# pms.net
KiCad netlist of a schematic drawn in EAGLE
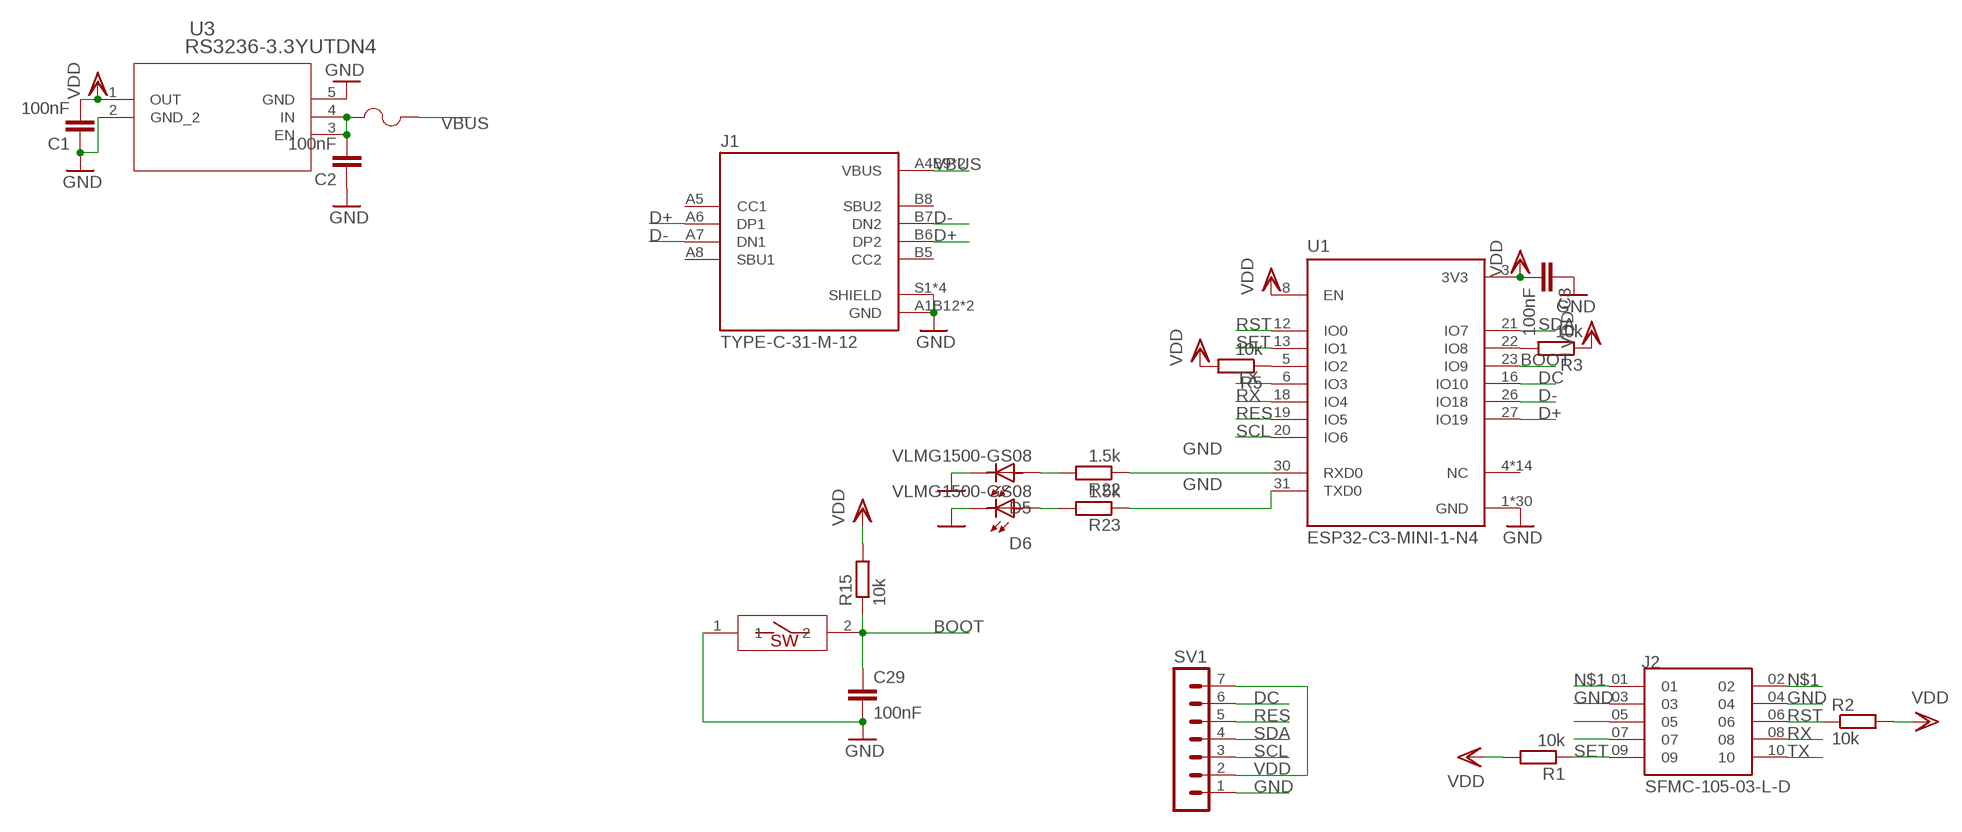
[diagram p0: schematic, sheet 1]

(export (version "E")
  (design (tool "Eeschema 10.0.6"))
  (components
    (comp (ref "C1")
      (value "100nF")
      (footprint "eagle-import:C0402")
      (libsource (lib "eagle-import") (part "CC0402"))
    )
    (comp (ref "C2")
      (value "100nF")
      (footprint "eagle-import:C0402")
      (libsource (lib "eagle-import") (part "CC0402"))
    )
    (comp (ref "C3")
      (value "100nF")
      (footprint "eagle-import:C0402")
      (libsource (lib "eagle-import") (part "CC0402"))
    )
    (comp (ref "C29")
      (value "100nF")
      (footprint "eagle-import:C0402")
      (libsource (lib "eagle-import") (part "CC0402"))
    )
    (comp (ref "D5")
      (value "VLMG1500-GS08")
      (footprint "eagle-import:LEDC1005X35N")
      (fields (field (name "MF") "Vishay"))
      (libsource (lib "eagle-import") (part "VLMG1500-GS08"))
    )
    (comp (ref "D6")
      (value "VLMG1500-GS08")
      (footprint "eagle-import:LEDC1005X35N")
      (fields (field (name "MF") "Vishay"))
      (libsource (lib "eagle-import") (part "VLMG1500-GS08"))
    )
    (comp (ref "F2")
      (value "1210L050YR1210LSERIES_LTF-L")
      (footprint "eagle-import:1210LSERIES_LTF-L")
      (fields (field (name "MANUFACTURER_PART_NUMBER") "1210L050YR"))
      (libsource (lib "eagle-import") (part "1210L050YR1210LSERIES_LTF-L"))
    )
    (comp (ref "J1")
      (value "TYPE-C-31-M-12")
      (footprint "eagle-import:HRO_TYPE-C-31-M-12")
      (fields (field (name "MF") "HRO Electronics Co., Ltd."))
      (libsource (lib "eagle-import") (part "TYPE-C-31-M-12"))
    )
    (comp (ref "J2")
      (value "SFMC-105-03-L-D")
      (footprint "eagle-import:SAMTEC_SFMC-105-03-L-D")
      (fields (field (name "MF") "Samtec"))
      (libsource (lib "eagle-import") (part "SFMC-105-03-L-D"))
    )
    (comp (ref "R1")
      (value "10k")
      (footprint "eagle-import:R0402")
      (libsource (lib "eagle-import") (part "RR0402"))
    )
    (comp (ref "R2")
      (value "10k")
      (footprint "eagle-import:R0402")
      (libsource (lib "eagle-import") (part "RR0402"))
    )
    (comp (ref "R3")
      (value "10k")
      (footprint "eagle-import:R0402")
      (libsource (lib "eagle-import") (part "RR0402"))
    )
    (comp (ref "R5")
      (value "10k")
      (footprint "eagle-import:R0402")
      (libsource (lib "eagle-import") (part "RR0402"))
    )
    (comp (ref "R15")
      (value "10k")
      (footprint "eagle-import:R0402")
      (libsource (lib "eagle-import") (part "RR0402"))
    )
    (comp (ref "R22")
      (value "1.5k")
      (footprint "eagle-import:R0402")
      (libsource (lib "eagle-import") (part "RR0402"))
    )
    (comp (ref "R23")
      (value "1.5k")
      (footprint "eagle-import:R0402")
      (libsource (lib "eagle-import") (part "RR0402"))
    )
    (comp (ref "RESET")
      (value "SMDSWITCH")
      (footprint "eagle-import:RESC4217X170")
      (libsource (lib "eagle-import") (part "SMDSWITCH"))
    )
    (comp (ref "SV1")
      (value "MA07-1")
      (footprint "eagle-import:MA07-1")
      (libsource (lib "eagle-import") (part "MA07-1"))
    )
    (comp (ref "U1")
      (value "ESP32-C3-MINI-1-N4")
      (footprint "eagle-import:XCVR_ESP32-C3-MINI-1-N4")
      (fields (field (name "MF") "Espressif Systems"))
      (libsource (lib "eagle-import") (part "ESP32-C3-MINI-1-N4"))
    )
    (comp (ref "U3")
      (value "RS3236-3.3YUTDN4")
      (footprint "eagle-import:UTDFN-1X1-4_JRT")
      (fields (field (name "COPYRIGHT") "Copyright (C) 2022 Ultra Librarian. All rights reserved."))
      (libsource (lib "eagle-import") (part "RS3236-3.3YUTDN4"))
    )
  )
  (nets
    (net (code "1") (name "/BOOT") (class "Default")
      (node (ref "C29") (pin "1") (pinfunction "1_1") (pintype "passive"))
      (node (ref "R15") (pin "1") (pinfunction "1_1") (pintype "passive"))
      (node (ref "RESET") (pin "2") (pinfunction "2_2") (pintype "bidirectional"))
      (node (ref "U1") (pin "23") (pinfunction "IO9_23") (pintype "bidirectional"))
    )
    (net (code "2") (name "/D+") (class "Default")
      (node (ref "J1") (pin "A6") (pinfunction "DP1_A6") (pintype "bidirectional"))
      (node (ref "J1") (pin "B6") (pinfunction "DP2_B6") (pintype "bidirectional"))
      (node (ref "U1") (pin "27") (pinfunction "IO19_27") (pintype "bidirectional"))
    )
    (net (code "3") (name "/D-") (class "Default")
      (node (ref "J1") (pin "A7") (pinfunction "DN1_A7") (pintype "bidirectional"))
      (node (ref "J1") (pin "B7") (pinfunction "DN2_B7") (pintype "bidirectional"))
      (node (ref "U1") (pin "26") (pinfunction "IO18_26") (pintype "bidirectional"))
    )
    (net (code "4") (name "/DC") (class "Default")
      (node (ref "SV1") (pin "6") (pinfunction "6_6") (pintype "passive"))
      (node (ref "U1") (pin "16") (pinfunction "IO10_16") (pintype "bidirectional"))
    )
    (net (code "5") (name "/N$1") (class "Default")
      (node (ref "C2") (pin "2") (pinfunction "2_2") (pintype "passive"))
      (node (ref "F2") (pin "2") (pinfunction "2_2") (pintype "passive"))
      (node (ref "J2") (pin "01") (pinfunction "01_01") (pintype "passive"))
      (node (ref "J2") (pin "02") (pinfunction "02_02") (pintype "passive"))
      (node (ref "U3") (pin "3") (pinfunction "EN_3") (pintype "input"))
      (node (ref "U3") (pin "4") (pinfunction "IN_4") (pintype "power_in"))
    )
    (net (code "6") (name "/RES") (class "Default")
      (node (ref "SV1") (pin "5") (pinfunction "5_5") (pintype "passive"))
      (node (ref "U1") (pin "19") (pinfunction "IO5_19") (pintype "bidirectional"))
    )
    (net (code "7") (name "/RST") (class "Default")
      (node (ref "J2") (pin "06") (pinfunction "06_06") (pintype "passive"))
      (node (ref "R2") (pin "1") (pinfunction "1_1") (pintype "passive"))
      (node (ref "U1") (pin "12") (pinfunction "IO0_12") (pintype "bidirectional"))
    )
    (net (code "8") (name "/RX") (class "Default")
      (node (ref "J2") (pin "08") (pinfunction "08_08") (pintype "passive"))
      (node (ref "U1") (pin "18") (pinfunction "IO4_18") (pintype "bidirectional"))
    )
    (net (code "9") (name "/SCL") (class "Default")
      (node (ref "SV1") (pin "3") (pinfunction "3_3") (pintype "passive"))
      (node (ref "U1") (pin "20") (pinfunction "IO6_20") (pintype "bidirectional"))
    )
    (net (code "10") (name "/SDA") (class "Default")
      (node (ref "SV1") (pin "4") (pinfunction "4_4") (pintype "passive"))
      (node (ref "U1") (pin "21") (pinfunction "IO7_21") (pintype "bidirectional"))
    )
    (net (code "11") (name "/SET") (class "Default")
      (node (ref "J2") (pin "09") (pinfunction "09_09") (pintype "passive"))
      (node (ref "R1") (pin "1") (pinfunction "1_1") (pintype "passive"))
      (node (ref "U1") (pin "13") (pinfunction "IO1_13") (pintype "bidirectional"))
    )
    (net (code "12") (name "/TX") (class "Default")
      (node (ref "J2") (pin "10") (pinfunction "10_10") (pintype "passive"))
      (node (ref "U1") (pin "6") (pinfunction "IO3_6") (pintype "bidirectional"))
    )
    (net (code "13") (name "/VBUS") (class "Default")
      (node (ref "F2") (pin "1") (pinfunction "1_1") (pintype "passive"))
      (node (ref "J1") (pin "A4B9") (pinfunction "VBUS_A4B9") (pintype "power_in"))
      (node (ref "J1") (pin "B4A9") (pinfunction "VBUS_B4A9") (pintype "power_in"))
    )
    (net (code "14") (name "GND") (class "Default")
      (node (ref "C1") (pin "1") (pinfunction "1_1") (pintype "passive"))
      (node (ref "C2") (pin "1") (pinfunction "1_1") (pintype "passive"))
      (node (ref "C29") (pin "2") (pinfunction "2_2") (pintype "passive"))
      (node (ref "C3") (pin "1") (pinfunction "1_1") (pintype "passive"))
      (node (ref "D5") (pin "2") (pinfunction "2_2") (pintype "passive"))
      (node (ref "D6") (pin "2") (pinfunction "2_2") (pintype "passive"))
      (node (ref "J1") (pin "A1B12") (pinfunction "GND_A1B12") (pintype "power_in"))
      (node (ref "J1") (pin "B1A12") (pinfunction "GND_B1A12") (pintype "power_in"))
      (node (ref "J1") (pin "S1") (pinfunction "SHIELD_S1") (pintype "passive"))
      (node (ref "J1") (pin "S2") (pinfunction "SHIELD_S2") (pintype "passive"))
      (node (ref "J1") (pin "S3") (pinfunction "SHIELD_S3") (pintype "passive"))
      (node (ref "J1") (pin "S4") (pinfunction "SHIELD_S4") (pintype "passive"))
      (node (ref "J2") (pin "03") (pinfunction "03_03") (pintype "passive"))
      (node (ref "J2") (pin "04") (pinfunction "04_04") (pintype "passive"))
      (node (ref "RESET") (pin "1") (pinfunction "1_1") (pintype "bidirectional"))
      (node (ref "SV1") (pin "1") (pinfunction "1_1") (pintype "passive"))
      (node (ref "U1") (pin "1") (pinfunction "GND_1") (pintype "power_in"))
      (node (ref "U1") (pin "11") (pinfunction "GND_11") (pintype "power_in"))
      (node (ref "U1") (pin "14") (pinfunction "GND_14") (pintype "power_in"))
      (node (ref "U1") (pin "2") (pinfunction "GND_2") (pintype "power_in"))
      (node (ref "U1") (pin "36") (pinfunction "GND_36") (pintype "power_in"))
      (node (ref "U1") (pin "37") (pinfunction "GND_37") (pintype "power_in"))
      (node (ref "U1") (pin "38") (pinfunction "GND_38") (pintype "power_in"))
      (node (ref "U1") (pin "39") (pinfunction "GND_39") (pintype "power_in"))
      (node (ref "U1") (pin "40") (pinfunction "GND_40") (pintype "power_in"))
      (node (ref "U1") (pin "41") (pinfunction "GND_41") (pintype "power_in"))
      (node (ref "U1") (pin "42") (pinfunction "GND_42") (pintype "power_in"))
      (node (ref "U1") (pin "43") (pinfunction "GND_43") (pintype "power_in"))
      (node (ref "U1") (pin "44") (pinfunction "GND_44") (pintype "power_in"))
      (node (ref "U1") (pin "45") (pinfunction "GND_45") (pintype "power_in"))
      (node (ref "U1") (pin "46") (pinfunction "GND_46") (pintype "power_in"))
      (node (ref "U1") (pin "47") (pinfunction "GND_47") (pintype "power_in"))
      (node (ref "U1") (pin "48") (pinfunction "GND_48") (pintype "power_in"))
      (node (ref "U1") (pin "49_1") (pinfunction "GND_49_1") (pintype "power_in"))
      (node (ref "U1") (pin "49_2") (pinfunction "GND_49_2") (pintype "power_in"))
      (node (ref "U1") (pin "49_3") (pinfunction "GND_49_3") (pintype "power_in"))
      (node (ref "U1") (pin "49_4") (pinfunction "GND_49_4") (pintype "power_in"))
      (node (ref "U1") (pin "49_5") (pinfunction "GND_49_5") (pintype "power_in"))
      (node (ref "U1") (pin "49_6") (pinfunction "GND_49_6") (pintype "power_in"))
      (node (ref "U1") (pin "49_7") (pinfunction "GND_49_7") (pintype "power_in"))
      (node (ref "U1") (pin "49_8") (pinfunction "GND_49_8") (pintype "power_in"))
      (node (ref "U1") (pin "49_9") (pinfunction "GND_49_9") (pintype "power_in"))
      (node (ref "U1") (pin "50") (pinfunction "GND_50") (pintype "power_in"))
      (node (ref "U1") (pin "51") (pinfunction "GND_51") (pintype "power_in"))
      (node (ref "U1") (pin "52") (pinfunction "GND_52") (pintype "power_in"))
      (node (ref "U1") (pin "53") (pinfunction "GND_53") (pintype "power_in"))
      (node (ref "U3") (pin "2") (pinfunction "GND_2_2") (pintype "passive"))
      (node (ref "U3") (pin "5") (pinfunction "GND_5") (pintype "passive"))
    )
    (net (code "15") (name "Net-(D5-Pad1)") (class "Default")
      (node (ref "D5") (pin "1") (pinfunction "1_1") (pintype "passive"))
      (node (ref "R22") (pin "2") (pinfunction "2_2") (pintype "passive"))
    )
    (net (code "16") (name "Net-(D6-Pad1)") (class "Default")
      (node (ref "D6") (pin "1") (pinfunction "1_1") (pintype "passive"))
      (node (ref "R23") (pin "2") (pinfunction "2_2") (pintype "passive"))
    )
    (net (code "17") (name "Net-(U1-IO2)") (class "Default")
      (node (ref "R5") (pin "1") (pinfunction "1_1") (pintype "passive"))
      (node (ref "U1") (pin "5") (pinfunction "IO2_5") (pintype "bidirectional"))
    )
    (net (code "18") (name "Net-(U1-IO8)") (class "Default")
      (node (ref "R3") (pin "2") (pinfunction "2_2") (pintype "passive"))
      (node (ref "U1") (pin "22") (pinfunction "IO8_22") (pintype "bidirectional"))
    )
    (net (code "19") (name "Net-(U1-RXD0)") (class "Default")
      (node (ref "R22") (pin "1") (pinfunction "1_1") (pintype "passive"))
      (node (ref "U1") (pin "30") (pinfunction "RXD0_30") (pintype "bidirectional"))
    )
    (net (code "20") (name "Net-(U1-TXD0)") (class "Default")
      (node (ref "R23") (pin "1") (pinfunction "1_1") (pintype "passive"))
      (node (ref "U1") (pin "31") (pinfunction "TXD0_31") (pintype "bidirectional"))
    )
    (net (code "21") (name "VDD") (class "Default")
      (node (ref "C1") (pin "2") (pinfunction "2_2") (pintype "passive"))
      (node (ref "C3") (pin "2") (pinfunction "2_2") (pintype "passive"))
      (node (ref "R1") (pin "2") (pinfunction "2_2") (pintype "passive"))
      (node (ref "R15") (pin "2") (pinfunction "2_2") (pintype "passive"))
      (node (ref "R2") (pin "2") (pinfunction "2_2") (pintype "passive"))
      (node (ref "R3") (pin "1") (pinfunction "1_1") (pintype "passive"))
      (node (ref "R5") (pin "2") (pinfunction "2_2") (pintype "passive"))
      (node (ref "SV1") (pin "2") (pinfunction "2_2") (pintype "passive"))
      (node (ref "SV1") (pin "7") (pinfunction "7_7") (pintype "passive"))
      (node (ref "U1") (pin "3") (pinfunction "3V3_3") (pintype "power_in"))
      (node (ref "U1") (pin "8") (pinfunction "EN_8") (pintype "input"))
      (node (ref "U3") (pin "1") (pinfunction "OUT_1") (pintype "output"))
    )
    (net (code "22") (name "unconnected-(J1-CC1-PadA5)") (class "Default")
      (node (ref "J1") (pin "A5") (pinfunction "CC1_A5") (pintype "bidirectional"))
    )
    (net (code "23") (name "unconnected-(J1-CC2-PadB5)") (class "Default")
      (node (ref "J1") (pin "B5") (pinfunction "CC2_B5") (pintype "bidirectional"))
    )
    (net (code "24") (name "unconnected-(J1-SBU1-PadA8)") (class "Default")
      (node (ref "J1") (pin "A8") (pinfunction "SBU1_A8") (pintype "bidirectional"))
    )
    (net (code "25") (name "unconnected-(J1-SBU2-PadB8)") (class "Default")
      (node (ref "J1") (pin "B8") (pinfunction "SBU2_B8") (pintype "bidirectional"))
    )
    (net (code "26") (name "unconnected-(J2-Pad05)") (class "Default")
      (node (ref "J2") (pin "05") (pinfunction "05_05") (pintype "passive"))
    )
    (net (code "27") (name "unconnected-(J2-Pad07)") (class "Default")
      (node (ref "J2") (pin "07") (pinfunction "07_07") (pintype "passive"))
    )
    (net (code "28") (name "unconnected-(U1-NC-Pad4)") (class "Default")
      (node (ref "U1") (pin "4") (pinfunction "NC_4") (pintype "no_connect"))
    )
    (net (code "29") (name "unconnected-(U1-NC-Pad7)") (class "Default")
      (node (ref "U1") (pin "7") (pinfunction "NC_7") (pintype "no_connect"))
    )
    (net (code "30") (name "unconnected-(U1-NC-Pad9)") (class "Default")
      (node (ref "U1") (pin "9") (pinfunction "NC_9") (pintype "no_connect"))
    )
    (net (code "31") (name "unconnected-(U1-NC-Pad10)") (class "Default")
      (node (ref "U1") (pin "10") (pinfunction "NC_10") (pintype "no_connect"))
    )
    (net (code "32") (name "unconnected-(U1-NC-Pad15)") (class "Default")
      (node (ref "U1") (pin "15") (pinfunction "NC_15") (pintype "no_connect"))
    )
    (net (code "33") (name "unconnected-(U1-NC-Pad17)") (class "Default")
      (node (ref "U1") (pin "17") (pinfunction "NC_17") (pintype "no_connect"))
    )
    (net (code "34") (name "unconnected-(U1-NC-Pad24)") (class "Default")
      (node (ref "U1") (pin "24") (pinfunction "NC_24") (pintype "no_connect"))
    )
    (net (code "35") (name "unconnected-(U1-NC-Pad25)") (class "Default")
      (node (ref "U1") (pin "25") (pinfunction "NC_25") (pintype "no_connect"))
    )
    (net (code "36") (name "unconnected-(U1-NC-Pad28)") (class "Default")
      (node (ref "U1") (pin "28") (pinfunction "NC_28") (pintype "no_connect"))
    )
    (net (code "37") (name "unconnected-(U1-NC-Pad29)") (class "Default")
      (node (ref "U1") (pin "29") (pinfunction "NC_29") (pintype "no_connect"))
    )
    (net (code "38") (name "unconnected-(U1-NC-Pad32)") (class "Default")
      (node (ref "U1") (pin "32") (pinfunction "NC_32") (pintype "no_connect"))
    )
    (net (code "39") (name "unconnected-(U1-NC-Pad33)") (class "Default")
      (node (ref "U1") (pin "33") (pinfunction "NC_33") (pintype "no_connect"))
    )
    (net (code "40") (name "unconnected-(U1-NC-Pad34)") (class "Default")
      (node (ref "U1") (pin "34") (pinfunction "NC_34") (pintype "no_connect"))
    )
    (net (code "41") (name "unconnected-(U1-NC-Pad35)") (class "Default")
      (node (ref "U1") (pin "35") (pinfunction "NC_35") (pintype "no_connect"))
    )
  )
)
